# M452s.net
KiCad netlist of a schematic drawn in EAGLE
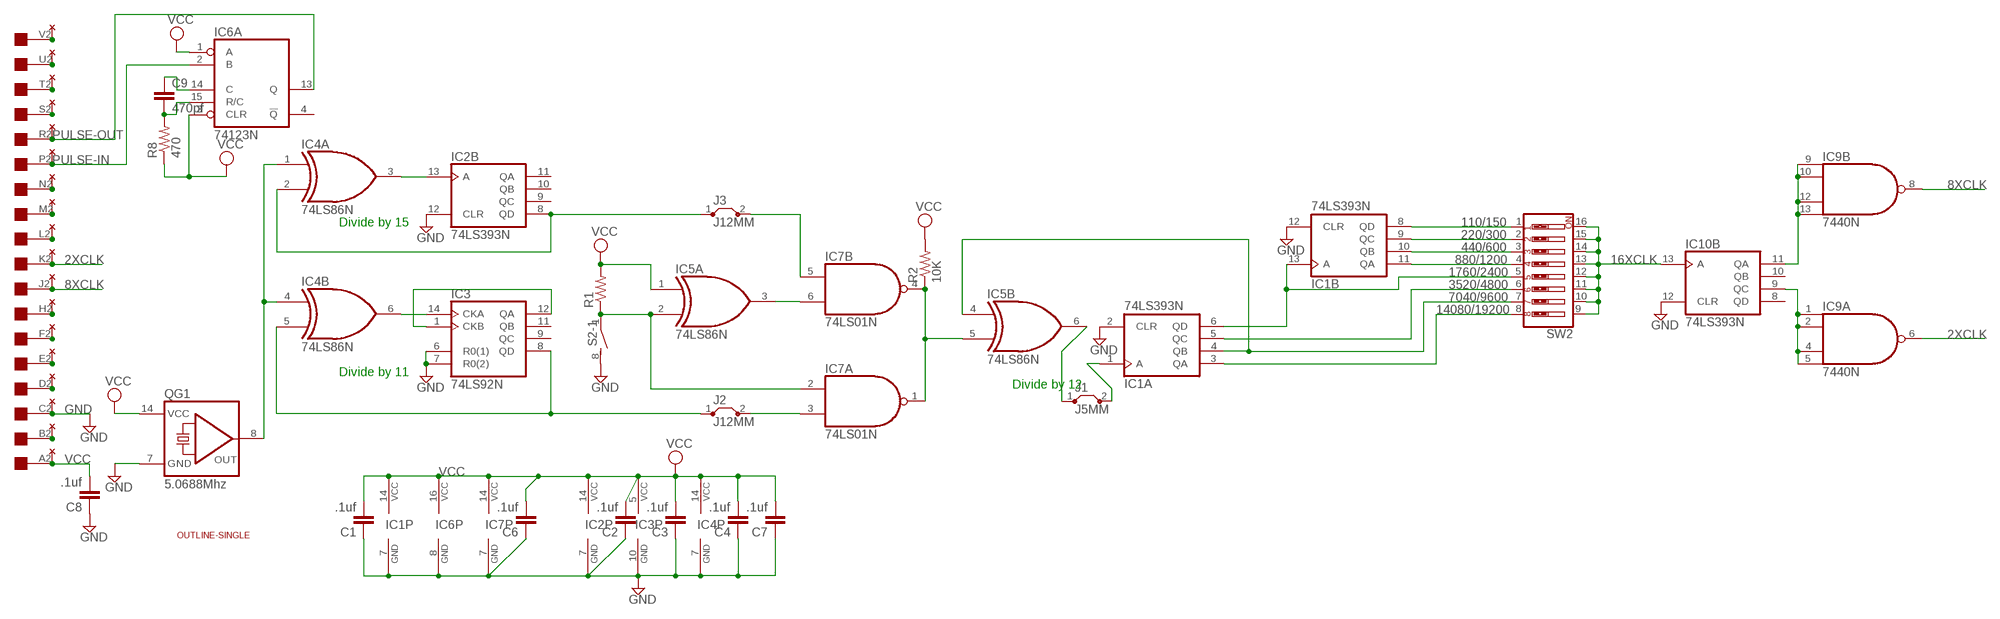
[diagram p0: schematic, sheet 1]

(export (version "E")
  (design (tool "Eeschema 10.0.6"))
  (components
    (comp (ref "C1")
      (value ".1uf")
      (footprint "eagle-import:C050-025X075")
      (libsource (lib "eagle-import") (part "C-EU050-025X075"))
    )
    (comp (ref "C2")
      (value ".1uf")
      (footprint "eagle-import:C050-025X075")
      (libsource (lib "eagle-import") (part "C-EU050-025X075"))
    )
    (comp (ref "C3")
      (value ".1uf")
      (footprint "eagle-import:C050-025X075")
      (libsource (lib "eagle-import") (part "C-EU050-025X075"))
    )
    (comp (ref "C4")
      (value ".1uf")
      (footprint "eagle-import:C050-025X075")
      (libsource (lib "eagle-import") (part "C-EU050-025X075"))
    )
    (comp (ref "C6")
      (value ".1uf")
      (footprint "eagle-import:C050-025X075")
      (libsource (lib "eagle-import") (part "C-EU050-025X075"))
    )
    (comp (ref "C7")
      (value ".1uf")
      (footprint "eagle-import:C050-025X075")
      (libsource (lib "eagle-import") (part "C-EU050-025X075"))
    )
    (comp (ref "C8")
      (value ".1uf")
      (footprint "eagle-import:C050-025X075")
      (libsource (lib "eagle-import") (part "C-EU050-025X075"))
    )
    (comp (ref "C9")
      (value "470pf")
      (footprint "eagle-import:C050-025X075")
      (libsource (lib "eagle-import") (part "C-EU050-025X075"))
    )
    (comp (ref "IC1")
      (value "74LS393N")
      (footprint "eagle-import:DIL14")
      (libsource (lib "eagle-import") (part "74393NLS"))
    )
    (comp (ref "IC2")
      (value "74LS393N")
      (footprint "eagle-import:DIL14")
      (libsource (lib "eagle-import") (part "74393NLS"))
    )
    (comp (ref "IC3")
      (value "74LS92N")
      (footprint "eagle-import:DIL14")
      (libsource (lib "eagle-import") (part "7492NLS"))
    )
    (comp (ref "IC4")
      (value "74LS86N")
      (footprint "eagle-import:DIL14")
      (libsource (lib "eagle-import") (part "7486NLS"))
    )
    (comp (ref "IC5")
      (value "74LS86N")
      (footprint "eagle-import:DIL14")
      (libsource (lib "eagle-import") (part "7486NLS"))
    )
    (comp (ref "IC6")
      (value "74123N")
      (footprint "eagle-import:DIL16")
      (libsource (lib "eagle-import") (part "74123N"))
    )
    (comp (ref "IC7")
      (value "74LS01N")
      (footprint "eagle-import:DIL14")
      (libsource (lib "eagle-import") (part "7401NLS"))
    )
    (comp (ref "IC9")
      (value "7440N")
      (footprint "eagle-import:DIL14")
      (libsource (lib "eagle-import") (part "7420NS"))
    )
    (comp (ref "IC10")
      (value "74LS393N")
      (footprint "eagle-import:DIL14")
      (libsource (lib "eagle-import") (part "74393NLS"))
    )
    (comp (ref "J1")
      (value "J5MM")
      (footprint "eagle-import:05")
      (libsource (lib "eagle-import") (part "J5MM"))
    )
    (comp (ref "J2")
      (value "J12MM")
      (footprint "eagle-import:12")
      (libsource (lib "eagle-import") (part "J12MM"))
    )
    (comp (ref "J3")
      (value "J12MM")
      (footprint "eagle-import:12")
      (libsource (lib "eagle-import") (part "J12MM"))
    )
    (comp (ref "QG1")
      (value "5.0688Mhz")
      (footprint "eagle-import:DIL14S")
      (libsource (lib "eagle-import") (part "QG5860"))
    )
    (comp (ref "R1")
      (value "R-US_0204/7")
      (footprint "eagle-import:0204_7")
      (libsource (lib "eagle-import") (part "R-US_0204/7"))
    )
    (comp (ref "R2")
      (value "10K")
      (footprint "eagle-import:0204_7")
      (libsource (lib "eagle-import") (part "R-US_0204/7"))
    )
    (comp (ref "R8")
      (value "470")
      (footprint "eagle-import:0204_7")
      (libsource (lib "eagle-import") (part "R-US_0204/7"))
    )
    (comp (ref "S2")
      (value "DIP04S")
      (footprint "eagle-import:DIP04S")
      (libsource (lib "eagle-import") (part "DIP04S"))
    )
    (comp (ref "SW2")
      (value "SW_DIP-8")
      (footprint "eagle-import:EDG-08")
      (libsource (lib "eagle-import") (part "SW_DIP-8"))
    )
    (comp (ref "U$2")
      (value "EDGE-1")
      (footprint "eagle-import:EDGE-CON1")
      (libsource (lib "eagle-import") (part "EDGE-1"))
    )
    (comp (ref "U$3")
      (value "OUTLINE-SINGLE")
      (footprint "eagle-import:SINGLE")
      (libsource (lib "eagle-import") (part "OUTLINE-SINGLE"))
    )
    (comp (ref "U$4")
      (value "THRU-HOLE1")
      (footprint "eagle-import:THRU-HOLE1")
      (libsource (lib "eagle-import") (part "THRU-HOLE1"))
    )
  )
  (nets
    (net (code "1") (name "/2XCLK") (class "Default")
      (node (ref "IC9") (pin "6") (pinfunction "O_6") (pintype "output"))
      (node (ref "U$2") (pin "K2") (pinfunction "1_K2") (pintype "bidirectional"))
      (node (ref "U$4") (pin "K2") (pinfunction "P$1_K2") (pintype "passive"))
    )
    (net (code "2") (name "/8XCLK") (class "Default")
      (node (ref "IC9") (pin "8") (pinfunction "O_8") (pintype "output"))
      (node (ref "U$2") (pin "J2") (pinfunction "1_J2") (pintype "bidirectional"))
      (node (ref "U$4") (pin "J2") (pinfunction "P$1_J2") (pintype "passive"))
    )
    (net (code "3") (name "/16XCLK") (class "Default")
      (node (ref "IC10") (pin "13") (pinfunction "A_13") (pintype "input"))
      (node (ref "SW2") (pin "10") (pinfunction "10_10") (pintype "passive"))
      (node (ref "SW2") (pin "11") (pinfunction "11_11") (pintype "passive"))
      (node (ref "SW2") (pin "12") (pinfunction "12_12") (pintype "passive"))
      (node (ref "SW2") (pin "13") (pinfunction "13_13") (pintype "passive"))
      (node (ref "SW2") (pin "14") (pinfunction "14_14") (pintype "passive"))
      (node (ref "SW2") (pin "15") (pinfunction "15_15") (pintype "passive"))
      (node (ref "SW2") (pin "16") (pinfunction "16_16") (pintype "passive"))
      (node (ref "SW2") (pin "9") (pinfunction "9_9") (pintype "passive"))
    )
    (net (code "4") (name "/110{slash}150") (class "Default")
      (node (ref "IC1") (pin "8") (pinfunction "QD_8") (pintype "output"))
      (node (ref "SW2") (pin "1") (pinfunction "1_1") (pintype "passive"))
    )
    (net (code "5") (name "/220{slash}300") (class "Default")
      (node (ref "IC1") (pin "9") (pinfunction "QC_9") (pintype "output"))
      (node (ref "SW2") (pin "2") (pinfunction "2_2") (pintype "passive"))
    )
    (net (code "6") (name "/440{slash}600") (class "Default")
      (node (ref "IC1") (pin "10") (pinfunction "QB_10") (pintype "output"))
      (node (ref "SW2") (pin "3") (pinfunction "3_3") (pintype "passive"))
    )
    (net (code "7") (name "/880{slash}1200") (class "Default")
      (node (ref "IC1") (pin "11") (pinfunction "QA_11") (pintype "output"))
      (node (ref "SW2") (pin "4") (pinfunction "4_4") (pintype "passive"))
    )
    (net (code "8") (name "/1760{slash}2400") (class "Default")
      (node (ref "IC1") (pin "13") (pinfunction "A_13") (pintype "input"))
      (node (ref "IC1") (pin "6") (pinfunction "QD_6") (pintype "output"))
      (node (ref "SW2") (pin "5") (pinfunction "5_5") (pintype "passive"))
    )
    (net (code "9") (name "/3520{slash}4800") (class "Default")
      (node (ref "IC1") (pin "5") (pinfunction "QC_5") (pintype "output"))
      (node (ref "SW2") (pin "6") (pinfunction "6_6") (pintype "passive"))
    )
    (net (code "10") (name "/7040{slash}9600") (class "Default")
      (node (ref "IC1") (pin "4") (pinfunction "QB_4") (pintype "output"))
      (node (ref "IC5") (pin "4") (pinfunction "I0_4") (pintype "input"))
      (node (ref "SW2") (pin "7") (pinfunction "7_7") (pintype "passive"))
    )
    (net (code "11") (name "/14080{slash}19200") (class "Default")
      (node (ref "IC1") (pin "3") (pinfunction "QA_3") (pintype "output"))
      (node (ref "SW2") (pin "8") (pinfunction "8_8") (pintype "passive"))
    )
    (net (code "12") (name "/PULSE-IN") (class "Default")
      (node (ref "IC6") (pin "2") (pinfunction "B_2") (pintype "input"))
      (node (ref "U$2") (pin "P2") (pinfunction "1_P2") (pintype "bidirectional"))
      (node (ref "U$4") (pin "P2") (pinfunction "P$1_P2") (pintype "passive"))
    )
    (net (code "13") (name "/PULSE-OUT") (class "Default")
      (node (ref "IC6") (pin "13") (pinfunction "Q_13") (pintype "output"))
      (node (ref "U$2") (pin "R2") (pinfunction "1_R2") (pintype "bidirectional"))
      (node (ref "U$4") (pin "R2") (pinfunction "P$1_R2") (pintype "passive"))
    )
    (net (code "14") (name "GND") (class "Default")
      (node (ref "C1") (pin "1") (pinfunction "1_1") (pintype "passive"))
      (node (ref "C2") (pin "1") (pinfunction "1_1") (pintype "passive"))
      (node (ref "C3") (pin "1") (pinfunction "1_1") (pintype "passive"))
      (node (ref "C4") (pin "1") (pinfunction "1_1") (pintype "passive"))
      (node (ref "C6") (pin "1") (pinfunction "1_1") (pintype "passive"))
      (node (ref "C7") (pin "1") (pinfunction "1_1") (pintype "passive"))
      (node (ref "C8") (pin "1") (pinfunction "1_1") (pintype "passive"))
      (node (ref "IC1") (pin "12") (pinfunction "CLR_12") (pintype "input"))
      (node (ref "IC1") (pin "2") (pinfunction "CLR_2") (pintype "input"))
      (node (ref "IC1") (pin "7") (pinfunction "GND_7") (pintype "power_in"))
      (node (ref "IC10") (pin "12") (pinfunction "CLR_12") (pintype "input"))
      (node (ref "IC2") (pin "12") (pinfunction "CLR_12") (pintype "input"))
      (node (ref "IC2") (pin "7") (pinfunction "GND_7") (pintype "power_in"))
      (node (ref "IC3") (pin "10") (pinfunction "GND_10") (pintype "power_in"))
      (node (ref "IC3") (pin "6") (pinfunction "R0(1)_6") (pintype "input"))
      (node (ref "IC3") (pin "7") (pinfunction "R0(2)_7") (pintype "input"))
      (node (ref "IC4") (pin "7") (pinfunction "GND_7") (pintype "power_in"))
      (node (ref "IC6") (pin "8") (pinfunction "GND_8") (pintype "power_in"))
      (node (ref "IC7") (pin "7") (pinfunction "GND_7") (pintype "power_in"))
      (node (ref "QG1") (pin "7") (pinfunction "GND_7") (pintype "power_in"))
      (node (ref "S2") (pin "8") (pinfunction "2_8") (pintype "passive"))
      (node (ref "U$2") (pin "C2") (pinfunction "1_C2") (pintype "bidirectional"))
      (node (ref "U$4") (pin "C2") (pinfunction "P$1_C2") (pintype "passive"))
    )
    (net (code "15") (name "Net-(IC1A-A)") (class "Default")
      (node (ref "IC1") (pin "1") (pinfunction "A_1") (pintype "input"))
      (node (ref "J1") (pin "2") (pinfunction "2_2") (pintype "passive"))
    )
    (net (code "16") (name "Net-(IC2B-A)") (class "Default")
      (node (ref "IC2") (pin "13") (pinfunction "A_13") (pintype "input"))
      (node (ref "IC4") (pin "3") (pinfunction "O_3") (pintype "output"))
    )
    (net (code "17") (name "Net-(IC2B-QD)") (class "Default")
      (node (ref "IC2") (pin "8") (pinfunction "QD_8") (pintype "output"))
      (node (ref "IC4") (pin "2") (pinfunction "I1_2") (pintype "input"))
      (node (ref "J3") (pin "1") (pinfunction "1_1") (pintype "passive"))
    )
    (net (code "18") (name "Net-(IC3A-CKA)") (class "Default")
      (node (ref "IC3") (pin "14") (pinfunction "CKA_14") (pintype "input"))
      (node (ref "IC4") (pin "6") (pinfunction "O_6") (pintype "output"))
    )
    (net (code "19") (name "Net-(IC3A-CKB)") (class "Default")
      (node (ref "IC3") (pin "1") (pinfunction "CKB_1") (pintype "input"))
      (node (ref "IC3") (pin "12") (pinfunction "QA_12") (pintype "output"))
    )
    (net (code "20") (name "Net-(IC3A-QD)") (class "Default")
      (node (ref "IC3") (pin "8") (pinfunction "QD_8") (pintype "output"))
      (node (ref "IC4") (pin "5") (pinfunction "I1_5") (pintype "input"))
      (node (ref "J2") (pin "1") (pinfunction "1_1") (pintype "passive"))
    )
    (net (code "21") (name "Net-(IC4A-I0)") (class "Default")
      (node (ref "IC4") (pin "1") (pinfunction "I0_1") (pintype "input"))
      (node (ref "IC4") (pin "4") (pinfunction "I0_4") (pintype "input"))
      (node (ref "QG1") (pin "8") (pinfunction "OUT_8") (pintype "output"))
    )
    (net (code "22") (name "Net-(IC5A-I1)") (class "Default")
      (node (ref "IC5") (pin "2") (pinfunction "I1_2") (pintype "input"))
      (node (ref "IC7") (pin "2") (pinfunction "I0_2") (pintype "input"))
      (node (ref "R1") (pin "1") (pinfunction "1_1") (pintype "passive"))
      (node (ref "S2") (pin "1") (pinfunction "1_1") (pintype "passive"))
    )
    (net (code "23") (name "Net-(IC5A-O)") (class "Default")
      (node (ref "IC5") (pin "3") (pinfunction "O_3") (pintype "output"))
      (node (ref "IC7") (pin "6") (pinfunction "I1_6") (pintype "input"))
    )
    (net (code "24") (name "Net-(IC5B-I1)") (class "Default")
      (node (ref "IC5") (pin "5") (pinfunction "I1_5") (pintype "input"))
      (node (ref "IC7") (pin "1") (pinfunction "O_1") (pintype "open_collector"))
      (node (ref "IC7") (pin "4") (pinfunction "O_4") (pintype "open_collector"))
      (node (ref "R2") (pin "1") (pinfunction "1_1") (pintype "passive"))
    )
    (net (code "25") (name "Net-(IC5B-O)") (class "Default")
      (node (ref "IC5") (pin "6") (pinfunction "O_6") (pintype "output"))
      (node (ref "J1") (pin "1") (pinfunction "1_1") (pintype "passive"))
    )
    (net (code "26") (name "Net-(IC6A-C)") (class "Default")
      (node (ref "C9") (pin "1") (pinfunction "1_1") (pintype "passive"))
      (node (ref "IC6") (pin "14") (pinfunction "C_14") (pintype "input"))
    )
    (net (code "27") (name "Net-(IC6A-R{slash}C)") (class "Default")
      (node (ref "C9") (pin "2") (pinfunction "2_2") (pintype "passive"))
      (node (ref "IC6") (pin "15") (pinfunction "R/C_15") (pintype "input"))
      (node (ref "R8") (pin "2") (pinfunction "2_2") (pintype "passive"))
    )
    (net (code "28") (name "Net-(IC7A-I1)") (class "Default")
      (node (ref "IC7") (pin "3") (pinfunction "I1_3") (pintype "input"))
      (node (ref "J2") (pin "2") (pinfunction "2_2") (pintype "passive"))
    )
    (net (code "29") (name "Net-(IC7B-I0)") (class "Default")
      (node (ref "IC7") (pin "5") (pinfunction "I0_5") (pintype "input"))
      (node (ref "J3") (pin "2") (pinfunction "2_2") (pintype "passive"))
    )
    (net (code "30") (name "Net-(IC10B-QA)") (class "Default")
      (node (ref "IC10") (pin "11") (pinfunction "QA_11") (pintype "output"))
      (node (ref "IC9") (pin "10") (pinfunction "I1_10") (pintype "input"))
      (node (ref "IC9") (pin "12") (pinfunction "I2_12") (pintype "input"))
      (node (ref "IC9") (pin "13") (pinfunction "I3_13") (pintype "input"))
      (node (ref "IC9") (pin "9") (pinfunction "I0_9") (pintype "input"))
    )
    (net (code "31") (name "Net-(IC10B-QC)") (class "Default")
      (node (ref "IC10") (pin "9") (pinfunction "QC_9") (pintype "output"))
      (node (ref "IC9") (pin "1") (pinfunction "I0_1") (pintype "input"))
      (node (ref "IC9") (pin "2") (pinfunction "I1_2") (pintype "input"))
      (node (ref "IC9") (pin "4") (pinfunction "I2_4") (pintype "input"))
      (node (ref "IC9") (pin "5") (pinfunction "I3_5") (pintype "input"))
    )
    (net (code "32") (name "Net-(U$2B-1)") (class "Default")
      (node (ref "U$2") (pin "B2") (pinfunction "1_B2") (pintype "bidirectional"))
      (node (ref "U$4") (pin "B2") (pinfunction "P$1_B2") (pintype "passive"))
    )
    (net (code "33") (name "Net-(U$2D-1)") (class "Default")
      (node (ref "U$2") (pin "D2") (pinfunction "1_D2") (pintype "bidirectional"))
      (node (ref "U$4") (pin "D2") (pinfunction "P$1_D2") (pintype "passive"))
    )
    (net (code "34") (name "Net-(U$2E-1)") (class "Default")
      (node (ref "U$2") (pin "E2") (pinfunction "1_E2") (pintype "bidirectional"))
      (node (ref "U$4") (pin "E2") (pinfunction "P$1_E2") (pintype "passive"))
    )
    (net (code "35") (name "Net-(U$2F-1)") (class "Default")
      (node (ref "U$2") (pin "F2") (pinfunction "1_F2") (pintype "bidirectional"))
      (node (ref "U$4") (pin "F2") (pinfunction "P$1_F2") (pintype "passive"))
    )
    (net (code "36") (name "Net-(U$2G-1)") (class "Default")
      (node (ref "U$2") (pin "H2") (pinfunction "1_H2") (pintype "bidirectional"))
      (node (ref "U$4") (pin "H2") (pinfunction "P$1_H2") (pintype "passive"))
    )
    (net (code "37") (name "Net-(U$2J-1)") (class "Default")
      (node (ref "U$2") (pin "L2") (pinfunction "1_L2") (pintype "bidirectional"))
      (node (ref "U$4") (pin "L2") (pinfunction "P$1_L2") (pintype "passive"))
    )
    (net (code "38") (name "Net-(U$2K-1)") (class "Default")
      (node (ref "U$2") (pin "M2") (pinfunction "1_M2") (pintype "bidirectional"))
      (node (ref "U$4") (pin "M2") (pinfunction "P$1_M2") (pintype "passive"))
    )
    (net (code "39") (name "Net-(U$2L-1)") (class "Default")
      (node (ref "U$2") (pin "N2") (pinfunction "1_N2") (pintype "bidirectional"))
      (node (ref "U$4") (pin "N2") (pinfunction "P$1_N2") (pintype "passive"))
    )
    (net (code "40") (name "Net-(U$2O-1)") (class "Default")
      (node (ref "U$2") (pin "S2") (pinfunction "1_S2") (pintype "bidirectional"))
      (node (ref "U$4") (pin "S2") (pinfunction "P$1_S2") (pintype "passive"))
    )
    (net (code "41") (name "Net-(U$2P-1)") (class "Default")
      (node (ref "U$2") (pin "T2") (pinfunction "1_T2") (pintype "bidirectional"))
      (node (ref "U$4") (pin "T2") (pinfunction "P$1_T2") (pintype "passive"))
    )
    (net (code "42") (name "Net-(U$2Q-1)") (class "Default")
      (node (ref "U$2") (pin "U2") (pinfunction "1_U2") (pintype "bidirectional"))
      (node (ref "U$4") (pin "U2") (pinfunction "P$1_U2") (pintype "passive"))
    )
    (net (code "43") (name "Net-(U$2R-1)") (class "Default")
      (node (ref "U$2") (pin "V2") (pinfunction "1_V2") (pintype "bidirectional"))
      (node (ref "U$4") (pin "V2") (pinfunction "P$1_V2") (pintype "passive"))
    )
    (net (code "44") (name "VCC") (class "Default")
      (node (ref "C1") (pin "2") (pinfunction "2_2") (pintype "passive"))
      (node (ref "C2") (pin "2") (pinfunction "2_2") (pintype "passive"))
      (node (ref "C3") (pin "2") (pinfunction "2_2") (pintype "passive"))
      (node (ref "C4") (pin "2") (pinfunction "2_2") (pintype "passive"))
      (node (ref "C6") (pin "2") (pinfunction "2_2") (pintype "passive"))
      (node (ref "C7") (pin "2") (pinfunction "2_2") (pintype "passive"))
      (node (ref "C8") (pin "2") (pinfunction "2_2") (pintype "passive"))
      (node (ref "IC1") (pin "14") (pinfunction "VCC_14") (pintype "power_in"))
      (node (ref "IC2") (pin "14") (pinfunction "VCC_14") (pintype "power_in"))
      (node (ref "IC3") (pin "5") (pinfunction "VCC_5") (pintype "power_in"))
      (node (ref "IC4") (pin "14") (pinfunction "VCC_14") (pintype "power_in"))
      (node (ref "IC5") (pin "1") (pinfunction "I0_1") (pintype "input"))
      (node (ref "IC6") (pin "1") (pinfunction "A_1") (pintype "input"))
      (node (ref "IC6") (pin "16") (pinfunction "VCC_16") (pintype "power_in"))
      (node (ref "IC6") (pin "3") (pinfunction "CLR_3") (pintype "input"))
      (node (ref "IC7") (pin "14") (pinfunction "VCC_14") (pintype "power_in"))
      (node (ref "QG1") (pin "14") (pinfunction "VCC_14") (pintype "power_in"))
      (node (ref "R1") (pin "2") (pinfunction "2_2") (pintype "passive"))
      (node (ref "R2") (pin "2") (pinfunction "2_2") (pintype "passive"))
      (node (ref "R8") (pin "1") (pinfunction "1_1") (pintype "passive"))
      (node (ref "U$2") (pin "A2") (pinfunction "1_A2") (pintype "bidirectional"))
      (node (ref "U$4") (pin "A2") (pinfunction "P$1_A2") (pintype "passive"))
    )
    (net (code "45") (name "unconnected-(IC2B-QA-Pad11)") (class "Default")
      (node (ref "IC2") (pin "11") (pinfunction "QA_11") (pintype "output"))
    )
    (net (code "46") (name "unconnected-(IC2B-QB-Pad10)") (class "Default")
      (node (ref "IC2") (pin "10") (pinfunction "QB_10") (pintype "output"))
    )
    (net (code "47") (name "unconnected-(IC2B-QC-Pad9)") (class "Default")
      (node (ref "IC2") (pin "9") (pinfunction "QC_9") (pintype "output"))
    )
    (net (code "48") (name "unconnected-(IC3A-QB-Pad11)") (class "Default")
      (node (ref "IC3") (pin "11") (pinfunction "QB_11") (pintype "output"))
    )
    (net (code "49") (name "unconnected-(IC3A-QC-Pad9)") (class "Default")
      (node (ref "IC3") (pin "9") (pinfunction "QC_9") (pintype "output"))
    )
    (net (code "50") (name "unconnected-(IC6A-~{Q}-Pad4)") (class "Default")
      (node (ref "IC6") (pin "4") (pinfunction "~{Q}_4") (pintype "output"))
    )
    (net (code "51") (name "unconnected-(IC10B-QB-Pad10)") (class "Default")
      (node (ref "IC10") (pin "10") (pinfunction "QB_10") (pintype "output"))
    )
    (net (code "52") (name "unconnected-(IC10B-QD-Pad8)") (class "Default")
      (node (ref "IC10") (pin "8") (pinfunction "QD_8") (pintype "output"))
    )
  )
)
